# CTM_Status_Station_Design_v24.net
KiCad netlist of a schematic drawn in EAGLE
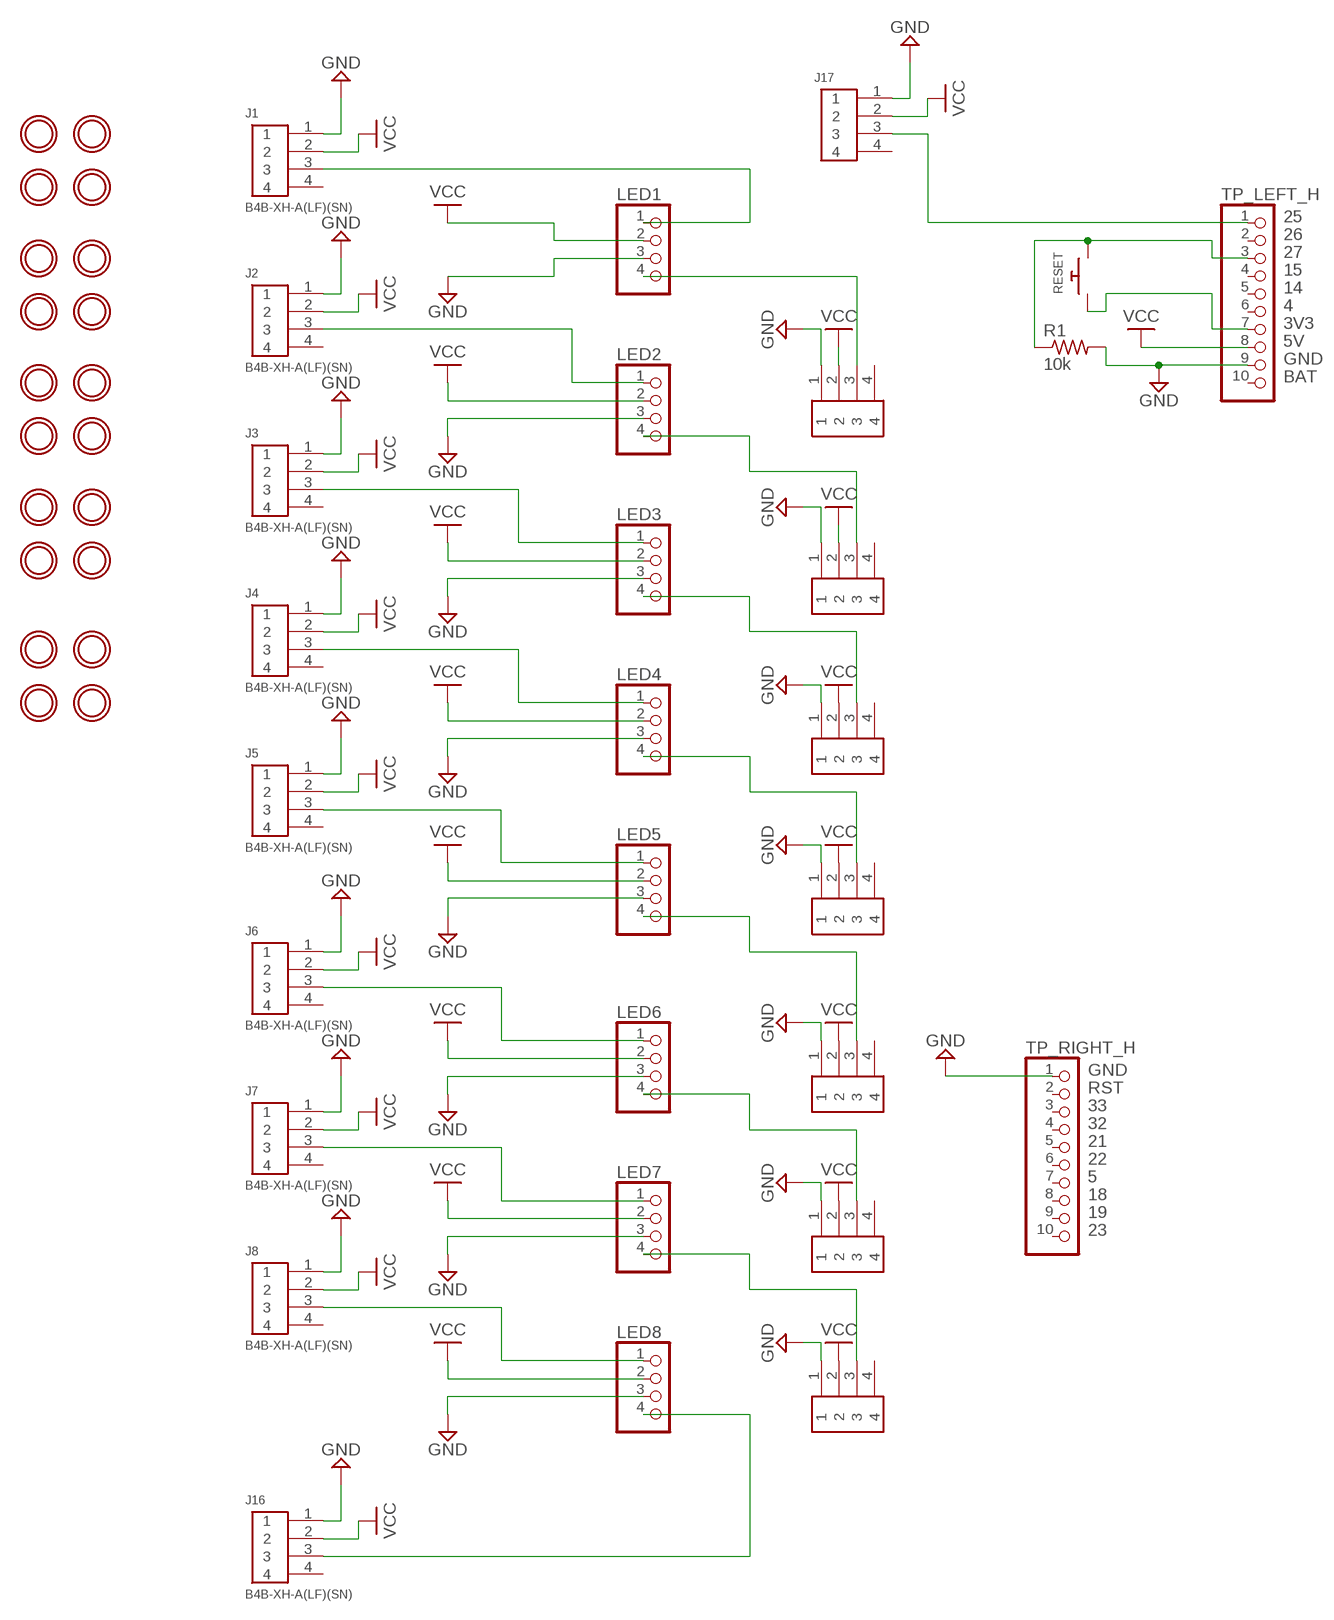
[diagram p0: schematic, sheet 1]

(export (version "E")
  (design (tool "Eeschema 10.0.6"))
  (components
    (comp (ref "J1")
      (value "B4B-XH-A(LF)(SN)")
      (footprint "eagle-import:B4B-XH-A(LF)(SN)")
      (fields
        (field (name "DIGIKEY_PARTNO") "455-2249-ND")
        (field (name "MANUFACTURER") "JST Sales America Inc.")
        (field (name "CREATED_BY") "PCBLayout.com")
      )
      (libsource (lib "eagle-import") (part "B4B-XH-A(LF)(SN)"))
    )
    (comp (ref "J2")
      (value "B4B-XH-A(LF)(SN)")
      (footprint "eagle-import:B4B-XH-A(LF)(SN)")
      (fields
        (field (name "DIGIKEY_PARTNO") "455-2249-ND")
        (field (name "MANUFACTURER") "JST Sales America Inc.")
        (field (name "CREATED_BY") "PCBLayout.com")
      )
      (libsource (lib "eagle-import") (part "B4B-XH-A(LF)(SN)"))
    )
    (comp (ref "J3")
      (value "B4B-XH-A(LF)(SN)")
      (footprint "eagle-import:B4B-XH-A(LF)(SN)")
      (fields
        (field (name "DIGIKEY_PARTNO") "455-2249-ND")
        (field (name "MANUFACTURER") "JST Sales America Inc.")
        (field (name "CREATED_BY") "PCBLayout.com")
      )
      (libsource (lib "eagle-import") (part "B4B-XH-A(LF)(SN)"))
    )
    (comp (ref "J4")
      (value "B4B-XH-A(LF)(SN)")
      (footprint "eagle-import:B4B-XH-A(LF)(SN)")
      (fields
        (field (name "DIGIKEY_PARTNO") "455-2249-ND")
        (field (name "MANUFACTURER") "JST Sales America Inc.")
        (field (name "CREATED_BY") "PCBLayout.com")
      )
      (libsource (lib "eagle-import") (part "B4B-XH-A(LF)(SN)"))
    )
    (comp (ref "J5")
      (value "B4B-XH-A(LF)(SN)")
      (footprint "eagle-import:B4B-XH-A(LF)(SN)")
      (fields
        (field (name "DIGIKEY_PARTNO") "455-2249-ND")
        (field (name "MANUFACTURER") "JST Sales America Inc.")
        (field (name "CREATED_BY") "PCBLayout.com")
      )
      (libsource (lib "eagle-import") (part "B4B-XH-A(LF)(SN)"))
    )
    (comp (ref "J6")
      (value "B4B-XH-A(LF)(SN)")
      (footprint "eagle-import:B4B-XH-A(LF)(SN)")
      (fields
        (field (name "DIGIKEY_PARTNO") "455-2249-ND")
        (field (name "MANUFACTURER") "JST Sales America Inc.")
        (field (name "CREATED_BY") "PCBLayout.com")
      )
      (libsource (lib "eagle-import") (part "B4B-XH-A(LF)(SN)"))
    )
    (comp (ref "J7")
      (value "B4B-XH-A(LF)(SN)")
      (footprint "eagle-import:B4B-XH-A(LF)(SN)")
      (fields
        (field (name "DIGIKEY_PARTNO") "455-2249-ND")
        (field (name "MANUFACTURER") "JST Sales America Inc.")
        (field (name "CREATED_BY") "PCBLayout.com")
      )
      (libsource (lib "eagle-import") (part "B4B-XH-A(LF)(SN)"))
    )
    (comp (ref "J8")
      (value "B4B-XH-A(LF)(SN)")
      (footprint "eagle-import:B4B-XH-A(LF)(SN)")
      (fields
        (field (name "DIGIKEY_PARTNO") "455-2249-ND")
        (field (name "MANUFACTURER") "JST Sales America Inc.")
        (field (name "CREATED_BY") "PCBLayout.com")
      )
      (libsource (lib "eagle-import") (part "B4B-XH-A(LF)(SN)"))
    )
    (comp (ref "J9")
      (value "B4B-XH-A(LF)(SN)")
      (footprint "eagle-import:B4B-XH-A(LF)(SN)")
      (fields
        (field (name "DIGIKEY_PARTNO") "455-2249-ND")
        (field (name "MANUFACTURER") "JST Sales America Inc.")
        (field (name "CREATED_BY") "PCBLayout.com")
      )
      (libsource (lib "eagle-import") (part "B4B-XH-A(LF)(SN)"))
    )
    (comp (ref "J10")
      (value "B4B-XH-A(LF)(SN)")
      (footprint "eagle-import:B4B-XH-A(LF)(SN)")
      (fields
        (field (name "DIGIKEY_PARTNO") "455-2249-ND")
        (field (name "MANUFACTURER") "JST Sales America Inc.")
        (field (name "CREATED_BY") "PCBLayout.com")
      )
      (libsource (lib "eagle-import") (part "B4B-XH-A(LF)(SN)"))
    )
    (comp (ref "J11")
      (value "B4B-XH-A(LF)(SN)")
      (footprint "eagle-import:B4B-XH-A(LF)(SN)")
      (fields
        (field (name "DIGIKEY_PARTNO") "455-2249-ND")
        (field (name "MANUFACTURER") "JST Sales America Inc.")
        (field (name "CREATED_BY") "PCBLayout.com")
      )
      (libsource (lib "eagle-import") (part "B4B-XH-A(LF)(SN)"))
    )
    (comp (ref "J12")
      (value "B4B-XH-A(LF)(SN)")
      (footprint "eagle-import:B4B-XH-A(LF)(SN)")
      (fields
        (field (name "DIGIKEY_PARTNO") "455-2249-ND")
        (field (name "MANUFACTURER") "JST Sales America Inc.")
        (field (name "CREATED_BY") "PCBLayout.com")
      )
      (libsource (lib "eagle-import") (part "B4B-XH-A(LF)(SN)"))
    )
    (comp (ref "J13")
      (value "B4B-XH-A(LF)(SN)")
      (footprint "eagle-import:B4B-XH-A(LF)(SN)")
      (fields
        (field (name "DIGIKEY_PARTNO") "455-2249-ND")
        (field (name "MANUFACTURER") "JST Sales America Inc.")
        (field (name "CREATED_BY") "PCBLayout.com")
      )
      (libsource (lib "eagle-import") (part "B4B-XH-A(LF)(SN)"))
    )
    (comp (ref "J14")
      (value "B4B-XH-A(LF)(SN)")
      (footprint "eagle-import:B4B-XH-A(LF)(SN)")
      (fields
        (field (name "DIGIKEY_PARTNO") "455-2249-ND")
        (field (name "MANUFACTURER") "JST Sales America Inc.")
        (field (name "CREATED_BY") "PCBLayout.com")
      )
      (libsource (lib "eagle-import") (part "B4B-XH-A(LF)(SN)"))
    )
    (comp (ref "J15")
      (value "B4B-XH-A(LF)(SN)")
      (footprint "eagle-import:B4B-XH-A(LF)(SN)")
      (fields
        (field (name "DIGIKEY_PARTNO") "455-2249-ND")
        (field (name "MANUFACTURER") "JST Sales America Inc.")
        (field (name "CREATED_BY") "PCBLayout.com")
      )
      (libsource (lib "eagle-import") (part "B4B-XH-A(LF)(SN)"))
    )
    (comp (ref "J16")
      (value "B4B-XH-A(LF)(SN)")
      (footprint "eagle-import:B4B-XH-A(LF)(SN)")
      (fields
        (field (name "DIGIKEY_PARTNO") "455-2249-ND")
        (field (name "MANUFACTURER") "JST Sales America Inc.")
        (field (name "CREATED_BY") "PCBLayout.com")
      )
      (libsource (lib "eagle-import") (part "B4B-XH-A(LF)(SN)"))
    )
    (comp (ref "J17")
      (value "B4B-XH-A(LF)(SN)")
      (footprint "eagle-import:B4B-XH-A(LF)(SN)")
      (fields
        (field (name "DIGIKEY_PARTNO") "455-2249-ND")
        (field (name "MANUFACTURER") "JST Sales America Inc.")
        (field (name "CREATED_BY") "PCBLayout.com")
      )
      (libsource (lib "eagle-import") (part "B4B-XH-A(LF)(SN)"))
    )
    (comp (ref "LED1")
      (value "PINHD-1X4")
      (footprint "eagle-import:1X04")
      (libsource (lib "eagle-import") (part "PINHD-1X4"))
    )
    (comp (ref "LED2")
      (value "PINHD-1X4")
      (footprint "eagle-import:1X04")
      (libsource (lib "eagle-import") (part "PINHD-1X4"))
    )
    (comp (ref "LED3")
      (value "PINHD-1X4")
      (footprint "eagle-import:1X04")
      (libsource (lib "eagle-import") (part "PINHD-1X4"))
    )
    (comp (ref "LED4")
      (value "PINHD-1X4")
      (footprint "eagle-import:1X04")
      (libsource (lib "eagle-import") (part "PINHD-1X4"))
    )
    (comp (ref "LED5")
      (value "PINHD-1X4")
      (footprint "eagle-import:1X04")
      (libsource (lib "eagle-import") (part "PINHD-1X4"))
    )
    (comp (ref "LED6")
      (value "PINHD-1X4")
      (footprint "eagle-import:1X04")
      (libsource (lib "eagle-import") (part "PINHD-1X4"))
    )
    (comp (ref "LED7")
      (value "PINHD-1X4")
      (footprint "eagle-import:1X04")
      (libsource (lib "eagle-import") (part "PINHD-1X4"))
    )
    (comp (ref "LED8")
      (value "PINHD-1X4")
      (footprint "eagle-import:1X04")
      (libsource (lib "eagle-import") (part "PINHD-1X4"))
    )
    (comp (ref "R1")
      (value "10k")
      (footprint "eagle-import:0207_7")
      (libsource (lib "eagle-import") (part "R-US_0207/7"))
    )
    (comp (ref "RESET")
      (value "SWITCH_PUSHBUTTONEVQ-PE")
      (footprint "eagle-import:TACT_PANA-EVQ")
      (libsource (lib "eagle-import") (part "SWITCH_PUSHBUTTONEVQ-PE"))
    )
    (comp (ref "TP_LEFT_H")
      (value "PINHD-1X10")
      (footprint "eagle-import:1X10")
      (libsource (lib "eagle-import") (part "PINHD-1X10"))
    )
    (comp (ref "TP_RIGHT_H")
      (value "PINHD-1X10")
      (footprint "eagle-import:1X10")
      (libsource (lib "eagle-import") (part "PINHD-1X10"))
    )
    (comp (ref "U$1")
      (value "MOUNTINGHOLE2.5")
      (footprint "eagle-import:MOUNTINGHOLE_2.5_PLATED")
      (fields (field (name "REV") "A"))
      (libsource (lib "eagle-import") (part "MOUNTINGHOLE2.5"))
    )
    (comp (ref "U$2")
      (value "MOUNTINGHOLE2.5")
      (footprint "eagle-import:MOUNTINGHOLE_2.5_PLATED")
      (fields (field (name "REV") "A"))
      (libsource (lib "eagle-import") (part "MOUNTINGHOLE2.5"))
    )
    (comp (ref "U$3")
      (value "MOUNTINGHOLE2.5")
      (footprint "eagle-import:MOUNTINGHOLE_2.5_PLATED")
      (fields (field (name "REV") "A"))
      (libsource (lib "eagle-import") (part "MOUNTINGHOLE2.5"))
    )
    (comp (ref "U$4")
      (value "MOUNTINGHOLE2.5")
      (footprint "eagle-import:MOUNTINGHOLE_2.5_PLATED")
      (fields (field (name "REV") "A"))
      (libsource (lib "eagle-import") (part "MOUNTINGHOLE2.5"))
    )
    (comp (ref "U$5")
      (value "MOUNTINGHOLE2.5")
      (footprint "eagle-import:MOUNTINGHOLE_2.5_PLATED")
      (fields (field (name "REV") "A"))
      (libsource (lib "eagle-import") (part "MOUNTINGHOLE2.5"))
    )
    (comp (ref "U$6")
      (value "MOUNTINGHOLE2.5")
      (footprint "eagle-import:MOUNTINGHOLE_2.5_PLATED")
      (fields (field (name "REV") "A"))
      (libsource (lib "eagle-import") (part "MOUNTINGHOLE2.5"))
    )
    (comp (ref "U$7")
      (value "MOUNTINGHOLE2.5")
      (footprint "eagle-import:MOUNTINGHOLE_2.5_PLATED")
      (fields (field (name "REV") "A"))
      (libsource (lib "eagle-import") (part "MOUNTINGHOLE2.5"))
    )
    (comp (ref "U$8")
      (value "MOUNTINGHOLE2.5")
      (footprint "eagle-import:MOUNTINGHOLE_2.5_PLATED")
      (fields (field (name "REV") "A"))
      (libsource (lib "eagle-import") (part "MOUNTINGHOLE2.5"))
    )
    (comp (ref "U$9")
      (value "MOUNTINGHOLE2.5")
      (footprint "eagle-import:MOUNTINGHOLE_2.5_PLATED")
      (fields (field (name "REV") "A"))
      (libsource (lib "eagle-import") (part "MOUNTINGHOLE2.5"))
    )
    (comp (ref "U$10")
      (value "MOUNTINGHOLE2.5")
      (footprint "eagle-import:MOUNTINGHOLE_2.5_PLATED")
      (fields (field (name "REV") "A"))
      (libsource (lib "eagle-import") (part "MOUNTINGHOLE2.5"))
    )
    (comp (ref "U$11")
      (value "MOUNTINGHOLE2.5")
      (footprint "eagle-import:MOUNTINGHOLE_2.5_PLATED")
      (fields (field (name "REV") "A"))
      (libsource (lib "eagle-import") (part "MOUNTINGHOLE2.5"))
    )
    (comp (ref "U$12")
      (value "MOUNTINGHOLE2.5")
      (footprint "eagle-import:MOUNTINGHOLE_2.5_PLATED")
      (fields (field (name "REV") "A"))
      (libsource (lib "eagle-import") (part "MOUNTINGHOLE2.5"))
    )
    (comp (ref "U$13")
      (value "MOUNTINGHOLE2.5")
      (footprint "eagle-import:MOUNTINGHOLE_2.5_PLATED")
      (fields (field (name "REV") "A"))
      (libsource (lib "eagle-import") (part "MOUNTINGHOLE2.5"))
    )
    (comp (ref "U$14")
      (value "MOUNTINGHOLE2.5")
      (footprint "eagle-import:MOUNTINGHOLE_2.5_PLATED")
      (fields (field (name "REV") "A"))
      (libsource (lib "eagle-import") (part "MOUNTINGHOLE2.5"))
    )
    (comp (ref "U$15")
      (value "MOUNTINGHOLE2.5")
      (footprint "eagle-import:MOUNTINGHOLE_2.5_PLATED")
      (fields (field (name "REV") "A"))
      (libsource (lib "eagle-import") (part "MOUNTINGHOLE2.5"))
    )
    (comp (ref "U$16")
      (value "MOUNTINGHOLE2.5")
      (footprint "eagle-import:MOUNTINGHOLE_2.5_PLATED")
      (fields (field (name "REV") "A"))
      (libsource (lib "eagle-import") (part "MOUNTINGHOLE2.5"))
    )
    (comp (ref "U$17")
      (value "MOUNTINGHOLE2.5")
      (footprint "eagle-import:MOUNTINGHOLE_2.5_PLATED")
      (fields (field (name "REV") "A"))
      (libsource (lib "eagle-import") (part "MOUNTINGHOLE2.5"))
    )
    (comp (ref "U$18")
      (value "MOUNTINGHOLE2.5")
      (footprint "eagle-import:MOUNTINGHOLE_2.5_PLATED")
      (fields (field (name "REV") "A"))
      (libsource (lib "eagle-import") (part "MOUNTINGHOLE2.5"))
    )
    (comp (ref "U$19")
      (value "MOUNTINGHOLE2.5")
      (footprint "eagle-import:MOUNTINGHOLE_2.5_PLATED")
      (fields (field (name "REV") "A"))
      (libsource (lib "eagle-import") (part "MOUNTINGHOLE2.5"))
    )
    (comp (ref "U$28")
      (value "MOUNTINGHOLE2.5")
      (footprint "eagle-import:MOUNTINGHOLE_2.5_PLATED")
      (fields (field (name "REV") "A"))
      (libsource (lib "eagle-import") (part "MOUNTINGHOLE2.5"))
    )
  )
  (nets
    (net (code "1") (name "GND") (class "Default")
      (node (ref "J1") (pin "1") (pinfunction "1_1") (pintype "passive"))
      (node (ref "J10") (pin "1") (pinfunction "1_1") (pintype "passive"))
      (node (ref "J11") (pin "1") (pinfunction "1_1") (pintype "passive"))
      (node (ref "J12") (pin "1") (pinfunction "1_1") (pintype "passive"))
      (node (ref "J13") (pin "1") (pinfunction "1_1") (pintype "passive"))
      (node (ref "J14") (pin "1") (pinfunction "1_1") (pintype "passive"))
      (node (ref "J15") (pin "1") (pinfunction "1_1") (pintype "passive"))
      (node (ref "J16") (pin "1") (pinfunction "1_1") (pintype "passive"))
      (node (ref "J17") (pin "1") (pinfunction "1_1") (pintype "passive"))
      (node (ref "J2") (pin "1") (pinfunction "1_1") (pintype "passive"))
      (node (ref "J3") (pin "1") (pinfunction "1_1") (pintype "passive"))
      (node (ref "J4") (pin "1") (pinfunction "1_1") (pintype "passive"))
      (node (ref "J5") (pin "1") (pinfunction "1_1") (pintype "passive"))
      (node (ref "J6") (pin "1") (pinfunction "1_1") (pintype "passive"))
      (node (ref "J7") (pin "1") (pinfunction "1_1") (pintype "passive"))
      (node (ref "J8") (pin "1") (pinfunction "1_1") (pintype "passive"))
      (node (ref "J9") (pin "1") (pinfunction "1_1") (pintype "passive"))
      (node (ref "LED1") (pin "3") (pinfunction "3_3") (pintype "passive"))
      (node (ref "LED2") (pin "3") (pinfunction "3_3") (pintype "passive"))
      (node (ref "LED3") (pin "3") (pinfunction "3_3") (pintype "passive"))
      (node (ref "LED4") (pin "3") (pinfunction "3_3") (pintype "passive"))
      (node (ref "LED5") (pin "3") (pinfunction "3_3") (pintype "passive"))
      (node (ref "LED6") (pin "3") (pinfunction "3_3") (pintype "passive"))
      (node (ref "LED7") (pin "3") (pinfunction "3_3") (pintype "passive"))
      (node (ref "LED8") (pin "3") (pinfunction "3_3") (pintype "passive"))
      (node (ref "R1") (pin "2") (pinfunction "2_2") (pintype "passive"))
      (node (ref "TP_LEFT_H") (pin "9") (pinfunction "9_9") (pintype "passive"))
      (node (ref "TP_RIGHT_H") (pin "1") (pinfunction "1_1") (pintype "passive"))
    )
    (net (code "2") (name "Net-(J1-Pad3)") (class "Default")
      (node (ref "J1") (pin "3") (pinfunction "3_3") (pintype "passive"))
      (node (ref "LED1") (pin "1") (pinfunction "1_1") (pintype "passive"))
    )
    (net (code "3") (name "Net-(J2-Pad3)") (class "Default")
      (node (ref "J2") (pin "3") (pinfunction "3_3") (pintype "passive"))
      (node (ref "LED2") (pin "1") (pinfunction "1_1") (pintype "passive"))
    )
    (net (code "4") (name "Net-(J3-Pad3)") (class "Default")
      (node (ref "J3") (pin "3") (pinfunction "3_3") (pintype "passive"))
      (node (ref "LED3") (pin "1") (pinfunction "1_1") (pintype "passive"))
    )
    (net (code "5") (name "Net-(J4-Pad3)") (class "Default")
      (node (ref "J4") (pin "3") (pinfunction "3_3") (pintype "passive"))
      (node (ref "LED4") (pin "1") (pinfunction "1_1") (pintype "passive"))
    )
    (net (code "6") (name "Net-(J5-Pad3)") (class "Default")
      (node (ref "J5") (pin "3") (pinfunction "3_3") (pintype "passive"))
      (node (ref "LED5") (pin "1") (pinfunction "1_1") (pintype "passive"))
    )
    (net (code "7") (name "Net-(J6-Pad3)") (class "Default")
      (node (ref "J6") (pin "3") (pinfunction "3_3") (pintype "passive"))
      (node (ref "LED6") (pin "1") (pinfunction "1_1") (pintype "passive"))
    )
    (net (code "8") (name "Net-(J7-Pad3)") (class "Default")
      (node (ref "J7") (pin "3") (pinfunction "3_3") (pintype "passive"))
      (node (ref "LED7") (pin "1") (pinfunction "1_1") (pintype "passive"))
    )
    (net (code "9") (name "Net-(J8-Pad3)") (class "Default")
      (node (ref "J8") (pin "3") (pinfunction "3_3") (pintype "passive"))
      (node (ref "LED8") (pin "1") (pinfunction "1_1") (pintype "passive"))
    )
    (net (code "10") (name "Net-(J9-Pad3)") (class "Default")
      (node (ref "J9") (pin "3") (pinfunction "3_3") (pintype "passive"))
      (node (ref "LED2") (pin "4") (pinfunction "4_4") (pintype "passive"))
    )
    (net (code "11") (name "Net-(J10-Pad3)") (class "Default")
      (node (ref "J10") (pin "3") (pinfunction "3_3") (pintype "passive"))
      (node (ref "LED1") (pin "4") (pinfunction "4_4") (pintype "passive"))
    )
    (net (code "12") (name "Net-(J11-Pad3)") (class "Default")
      (node (ref "J11") (pin "3") (pinfunction "3_3") (pintype "passive"))
      (node (ref "LED3") (pin "4") (pinfunction "4_4") (pintype "passive"))
    )
    (net (code "13") (name "Net-(J12-Pad3)") (class "Default")
      (node (ref "J12") (pin "3") (pinfunction "3_3") (pintype "passive"))
      (node (ref "LED4") (pin "4") (pinfunction "4_4") (pintype "passive"))
    )
    (net (code "14") (name "Net-(J13-Pad3)") (class "Default")
      (node (ref "J13") (pin "3") (pinfunction "3_3") (pintype "passive"))
      (node (ref "LED5") (pin "4") (pinfunction "4_4") (pintype "passive"))
    )
    (net (code "15") (name "Net-(J14-Pad3)") (class "Default")
      (node (ref "J14") (pin "3") (pinfunction "3_3") (pintype "passive"))
      (node (ref "LED6") (pin "4") (pinfunction "4_4") (pintype "passive"))
    )
    (net (code "16") (name "Net-(J15-Pad3)") (class "Default")
      (node (ref "J15") (pin "3") (pinfunction "3_3") (pintype "passive"))
      (node (ref "LED7") (pin "4") (pinfunction "4_4") (pintype "passive"))
    )
    (net (code "17") (name "Net-(J16-Pad3)") (class "Default")
      (node (ref "J16") (pin "3") (pinfunction "3_3") (pintype "passive"))
      (node (ref "LED8") (pin "4") (pinfunction "4_4") (pintype "passive"))
    )
    (net (code "18") (name "Net-(J17-Pad3)") (class "Default")
      (node (ref "J17") (pin "3") (pinfunction "3_3") (pintype "passive"))
      (node (ref "TP_LEFT_H") (pin "1") (pinfunction "1_1") (pintype "passive"))
    )
    (net (code "19") (name "Net-(R1-Pad1)") (class "Default")
      (node (ref "R1") (pin "1") (pinfunction "1_1") (pintype "passive"))
      (node (ref "RESET") (pin "P$2") (pinfunction "P$2_P$2") (pintype "passive"))
      (node (ref "TP_LEFT_H") (pin "3") (pinfunction "3_3") (pintype "passive"))
    )
    (net (code "20") (name "Net-(RESET-PadP$1)") (class "Default")
      (node (ref "RESET") (pin "P$1") (pinfunction "P$1_P$1") (pintype "passive"))
      (node (ref "TP_LEFT_H") (pin "7") (pinfunction "7_7") (pintype "passive"))
    )
    (net (code "21") (name "VCC") (class "Default")
      (node (ref "J1") (pin "2") (pinfunction "2_2") (pintype "passive"))
      (node (ref "J10") (pin "2") (pinfunction "2_2") (pintype "passive"))
      (node (ref "J11") (pin "2") (pinfunction "2_2") (pintype "passive"))
      (node (ref "J12") (pin "2") (pinfunction "2_2") (pintype "passive"))
      (node (ref "J13") (pin "2") (pinfunction "2_2") (pintype "passive"))
      (node (ref "J14") (pin "2") (pinfunction "2_2") (pintype "passive"))
      (node (ref "J15") (pin "2") (pinfunction "2_2") (pintype "passive"))
      (node (ref "J16") (pin "2") (pinfunction "2_2") (pintype "passive"))
      (node (ref "J17") (pin "2") (pinfunction "2_2") (pintype "passive"))
      (node (ref "J2") (pin "2") (pinfunction "2_2") (pintype "passive"))
      (node (ref "J3") (pin "2") (pinfunction "2_2") (pintype "passive"))
      (node (ref "J4") (pin "2") (pinfunction "2_2") (pintype "passive"))
      (node (ref "J5") (pin "2") (pinfunction "2_2") (pintype "passive"))
      (node (ref "J6") (pin "2") (pinfunction "2_2") (pintype "passive"))
      (node (ref "J7") (pin "2") (pinfunction "2_2") (pintype "passive"))
      (node (ref "J8") (pin "2") (pinfunction "2_2") (pintype "passive"))
      (node (ref "J9") (pin "2") (pinfunction "2_2") (pintype "passive"))
      (node (ref "LED1") (pin "2") (pinfunction "2_2") (pintype "passive"))
      (node (ref "LED2") (pin "2") (pinfunction "2_2") (pintype "passive"))
      (node (ref "LED3") (pin "2") (pinfunction "2_2") (pintype "passive"))
      (node (ref "LED4") (pin "2") (pinfunction "2_2") (pintype "passive"))
      (node (ref "LED5") (pin "2") (pinfunction "2_2") (pintype "passive"))
      (node (ref "LED6") (pin "2") (pinfunction "2_2") (pintype "passive"))
      (node (ref "LED7") (pin "2") (pinfunction "2_2") (pintype "passive"))
      (node (ref "LED8") (pin "2") (pinfunction "2_2") (pintype "passive"))
      (node (ref "TP_LEFT_H") (pin "8") (pinfunction "8_8") (pintype "passive"))
    )
    (net (code "22") (name "unconnected-(J1-Pad4)") (class "Default")
      (node (ref "J1") (pin "4") (pinfunction "4_4") (pintype "passive"))
    )
    (net (code "23") (name "unconnected-(J2-Pad4)") (class "Default")
      (node (ref "J2") (pin "4") (pinfunction "4_4") (pintype "passive"))
    )
    (net (code "24") (name "unconnected-(J3-Pad4)") (class "Default")
      (node (ref "J3") (pin "4") (pinfunction "4_4") (pintype "passive"))
    )
    (net (code "25") (name "unconnected-(J4-Pad4)") (class "Default")
      (node (ref "J4") (pin "4") (pinfunction "4_4") (pintype "passive"))
    )
    (net (code "26") (name "unconnected-(J5-Pad4)") (class "Default")
      (node (ref "J5") (pin "4") (pinfunction "4_4") (pintype "passive"))
    )
    (net (code "27") (name "unconnected-(J6-Pad4)") (class "Default")
      (node (ref "J6") (pin "4") (pinfunction "4_4") (pintype "passive"))
    )
    (net (code "28") (name "unconnected-(J7-Pad4)") (class "Default")
      (node (ref "J7") (pin "4") (pinfunction "4_4") (pintype "passive"))
    )
    (net (code "29") (name "unconnected-(J8-Pad4)") (class "Default")
      (node (ref "J8") (pin "4") (pinfunction "4_4") (pintype "passive"))
    )
    (net (code "30") (name "unconnected-(J9-Pad4)") (class "Default")
      (node (ref "J9") (pin "4") (pinfunction "4_4") (pintype "passive"))
    )
    (net (code "31") (name "unconnected-(J10-Pad4)") (class "Default")
      (node (ref "J10") (pin "4") (pinfunction "4_4") (pintype "passive"))
    )
    (net (code "32") (name "unconnected-(J11-Pad4)") (class "Default")
      (node (ref "J11") (pin "4") (pinfunction "4_4") (pintype "passive"))
    )
    (net (code "33") (name "unconnected-(J12-Pad4)") (class "Default")
      (node (ref "J12") (pin "4") (pinfunction "4_4") (pintype "passive"))
    )
    (net (code "34") (name "unconnected-(J13-Pad4)") (class "Default")
      (node (ref "J13") (pin "4") (pinfunction "4_4") (pintype "passive"))
    )
    (net (code "35") (name "unconnected-(J14-Pad4)") (class "Default")
      (node (ref "J14") (pin "4") (pinfunction "4_4") (pintype "passive"))
    )
    (net (code "36") (name "unconnected-(J15-Pad4)") (class "Default")
      (node (ref "J15") (pin "4") (pinfunction "4_4") (pintype "passive"))
    )
    (net (code "37") (name "unconnected-(J16-Pad4)") (class "Default")
      (node (ref "J16") (pin "4") (pinfunction "4_4") (pintype "passive"))
    )
    (net (code "38") (name "unconnected-(J17-Pad4)") (class "Default")
      (node (ref "J17") (pin "4") (pinfunction "4_4") (pintype "passive"))
    )
    (net (code "39") (name "unconnected-(TP_LEFT_H-Pad2)") (class "Default")
      (node (ref "TP_LEFT_H") (pin "2") (pinfunction "2_2") (pintype "passive"))
    )
    (net (code "40") (name "unconnected-(TP_LEFT_H-Pad4)") (class "Default")
      (node (ref "TP_LEFT_H") (pin "4") (pinfunction "4_4") (pintype "passive"))
    )
    (net (code "41") (name "unconnected-(TP_LEFT_H-Pad5)") (class "Default")
      (node (ref "TP_LEFT_H") (pin "5") (pinfunction "5_5") (pintype "passive"))
    )
    (net (code "42") (name "unconnected-(TP_LEFT_H-Pad6)") (class "Default")
      (node (ref "TP_LEFT_H") (pin "6") (pinfunction "6_6") (pintype "passive"))
    )
    (net (code "43") (name "unconnected-(TP_LEFT_H-Pad10)") (class "Default")
      (node (ref "TP_LEFT_H") (pin "10") (pinfunction "10_10") (pintype "passive"))
    )
    (net (code "44") (name "unconnected-(TP_RIGHT_H-Pad2)") (class "Default")
      (node (ref "TP_RIGHT_H") (pin "2") (pinfunction "2_2") (pintype "passive"))
    )
    (net (code "45") (name "unconnected-(TP_RIGHT_H-Pad3)") (class "Default")
      (node (ref "TP_RIGHT_H") (pin "3") (pinfunction "3_3") (pintype "passive"))
    )
    (net (code "46") (name "unconnected-(TP_RIGHT_H-Pad4)") (class "Default")
      (node (ref "TP_RIGHT_H") (pin "4") (pinfunction "4_4") (pintype "passive"))
    )
    (net (code "47") (name "unconnected-(TP_RIGHT_H-Pad5)") (class "Default")
      (node (ref "TP_RIGHT_H") (pin "5") (pinfunction "5_5") (pintype "passive"))
    )
    (net (code "48") (name "unconnected-(TP_RIGHT_H-Pad6)") (class "Default")
      (node (ref "TP_RIGHT_H") (pin "6") (pinfunction "6_6") (pintype "passive"))
    )
    (net (code "49") (name "unconnected-(TP_RIGHT_H-Pad7)") (class "Default")
      (node (ref "TP_RIGHT_H") (pin "7") (pinfunction "7_7") (pintype "passive"))
    )
    (net (code "50") (name "unconnected-(TP_RIGHT_H-Pad8)") (class "Default")
      (node (ref "TP_RIGHT_H") (pin "8") (pinfunction "8_8") (pintype "passive"))
    )
    (net (code "51") (name "unconnected-(TP_RIGHT_H-Pad9)") (class "Default")
      (node (ref "TP_RIGHT_H") (pin "9") (pinfunction "9_9") (pintype "passive"))
    )
    (net (code "52") (name "unconnected-(TP_RIGHT_H-Pad10)") (class "Default")
      (node (ref "TP_RIGHT_H") (pin "10") (pinfunction "10_10") (pintype "passive"))
    )
  )
)
